# CHIBI_INPUT2_20171126.net
KiCad netlist of a schematic drawn in Altium Designer
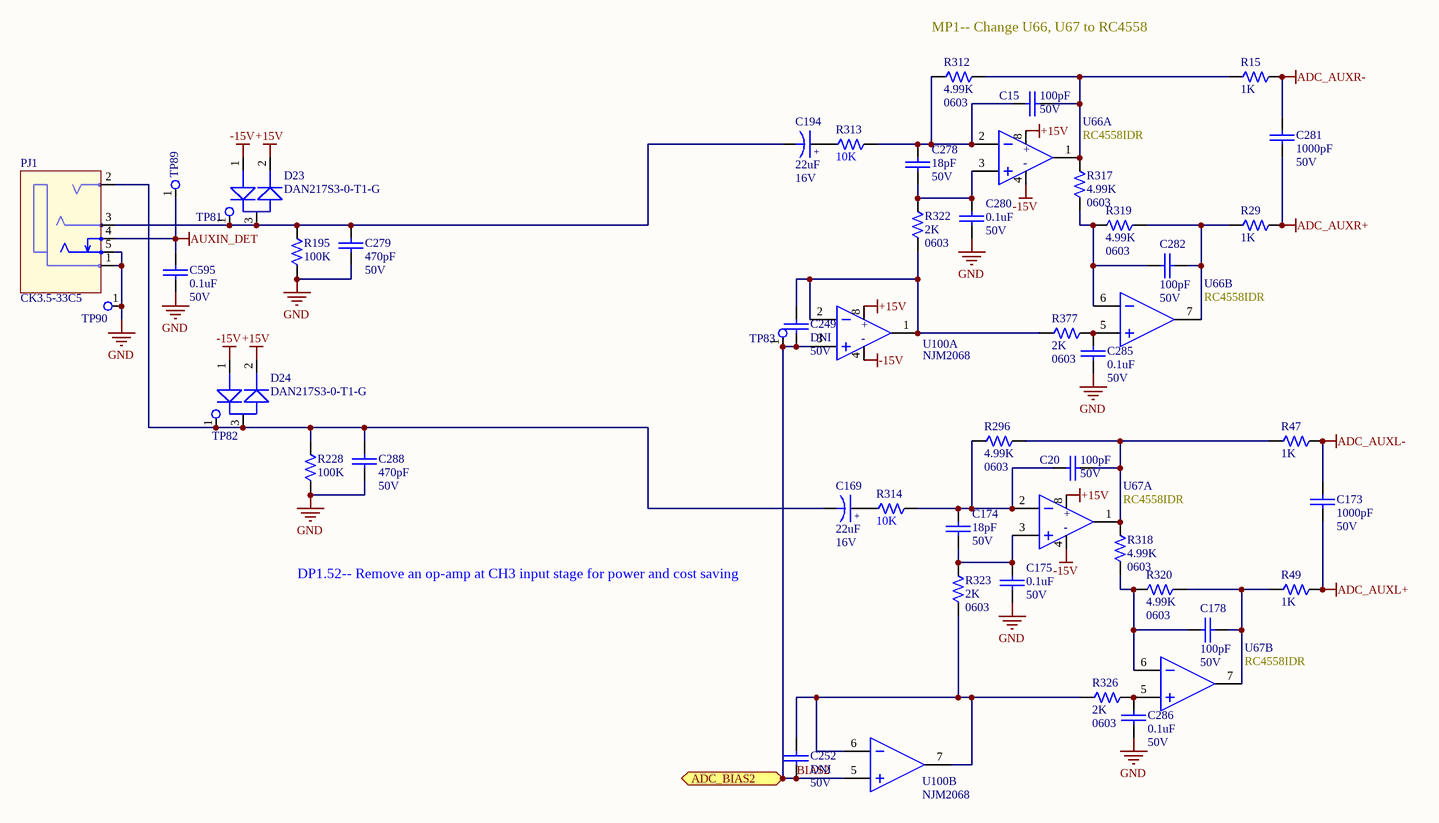
[diagram p0: CHIBI_INPUT2_20171126.SchDoc]

(export (version "E")
  (design (tool "Eeschema 10.0.6"))
  (components
    (comp (ref "C15")
      (value "100pF")
      (footprint "CAPC0603-RW")
      (description "GP CHIP CAP 100pF 50V 5% 0603 TYPE NPO")
      (fields
        (field (name "TOLERANCE") "5%")
        (field (name "VOLTAGE") "50V")
        (field (name "Comment") "PXL410370-1010")
      )
      (libsource (lib "P-Capacitors") (part "CAP0603 100pF 50V 5% - PXL410370-1010"))
    )
    (comp (ref "C20")
      (value "100pF")
      (footprint "CAPC0603-RW")
      (description "GP CHIP CAP 100pF 50V 5% 0603 TYPE NPO")
      (fields
        (field (name "TOLERANCE") "5%")
        (field (name "VOLTAGE") "50V")
        (field (name "Comment") "PXL410370-1010")
      )
      (libsource (lib "P-Capacitors") (part "CAP0603 100pF 50V 5% - PXL410370-1010"))
    )
    (comp (ref "C169")
      (value "22uF")
      (footprint "CASE - B")
      (description "E 22UF 16V +-20% 4X5.4M CK1C220M-CRC54 G")
      (fields
        (field (name "MFG") "NORMAL")
        (field (name "MFG PART") "CK1C220M-CRC54")
        (field (name "VOLTAGE") "16V")
      )
      (libsource (lib "P-Capacitors") (part "CAP E 22uF 16V 20% SMD_CASE-B"))
    )
    (comp (ref "C173")
      (value "1000pF")
      (footprint "CAPC0603-RW")
      (description "CHIP CAP 1000pF 50V 5% 0603 TYPE NPO")
      (fields
        (field (name "TOLERANCE") "5%")
        (field (name "VOLTAGE") "50V")
        (field (name "Comment") "PXL410370-1020")
      )
      (libsource (lib "P-Capacitors") (part "CAP0603 1000pF 50V 5% - PXL410370-1020"))
    )
    (comp (ref "C174")
      (value "18pF")
      (footprint "P-Capacitors:CAPC0603-RW")
      (description "CHIP CAP 18pF 50V 5% 0603 TYPE NPO")
      (fields
        (field (name "TOLERANCE") "5%")
        (field (name "VOLTAGE") "50V")
        (field (name "Comment") "PXL410370-1800")
      )
      (libsource (lib "P-Capacitors") (part "CAP0603 18pF 50V 5% - PXL410370-1800"))
    )
    (comp (ref "C175")
      (value "0.1uF")
      (footprint "CAPC0603-RW")
      (description "GP CHIP CAP 0.1uF 50V 10% 0603 TYPE X7R")
      (fields
        (field (name "TOLERANCE") "10%")
        (field (name "VOLTAGE") "50V")
        (field (name "Comment") "PXL456470-1040")
      )
      (libsource (lib "P-Capacitors") (part "CAP0603 0.1uF 50V 10% - PXL456470-1040"))
    )
    (comp (ref "C178")
      (value "100pF")
      (footprint "CAPC0603-RW")
      (description "GP CHIP CAP 100pF 50V 5% 0603 TYPE NPO")
      (fields
        (field (name "TOLERANCE") "5%")
        (field (name "VOLTAGE") "50V")
        (field (name "Comment") "PXL410370-1010")
      )
      (libsource (lib "P-Capacitors") (part "CAP0603 100pF 50V 5% - PXL410370-1010"))
    )
    (comp (ref "C194")
      (value "22uF")
      (footprint "CASE - B")
      (description "E 22UF 16V +-20% 4X5.4M CK1C220M-CRC54 G")
      (fields
        (field (name "MFG") "NORMAL")
        (field (name "MFG PART") "CK1C220M-CRC54")
        (field (name "VOLTAGE") "16V")
      )
      (libsource (lib "P-Capacitors") (part "CAP E 22uF 16V 20% SMD_CASE-B"))
    )
    (comp (ref "C249")
      (value "DNI")
      (footprint "CAPC0402-RW")
      (fields
        (field (name "TOLERANCE") "10%")
        (field (name "VOLTAGE") "50V")
        (field (name "CREATE_NAME") "Nathan")
      )
      (libsource (lib "P-Capacitors") (part "CAP0402 0.1uF 50V_10%_X7R_TDK"))
    )
    (comp (ref "C252")
      (value "DNI")
      (footprint "CAPC0402-RW")
      (fields
        (field (name "TOLERANCE") "10%")
        (field (name "VOLTAGE") "50V")
        (field (name "CREATE_NAME") "Nathan")
      )
      (libsource (lib "P-Capacitors") (part "CAP0402 0.1uF 50V_10%_X7R_TDK"))
    )
    (comp (ref "C278")
      (value "18pF")
      (footprint "P-Capacitors:CAPC0603-RW")
      (description "CHIP CAP 18pF 50V 5% 0603 TYPE NPO")
      (fields
        (field (name "TOLERANCE") "5%")
        (field (name "VOLTAGE") "50V")
        (field (name "Comment") "PXL410370-1800")
      )
      (libsource (lib "P-Capacitors") (part "CAP0603 18pF 50V 5% - PXL410370-1800"))
    )
    (comp (ref "C279")
      (value "470pF")
      (footprint "P-Capacitors:CAPC0603-RW")
      (description "GP CHIP CAP 470pF 50V 5% 0603 NPO")
      (fields
        (field (name "TOLERANCE") "5%")
        (field (name "VOLTAGE") "50V")
        (field (name "Comment") "PXL410370-4710")
      )
      (libsource (lib "P-Capacitors") (part "CAP0603 470pF 50V 5% - PXL410370-4710"))
    )
    (comp (ref "C280")
      (value "0.1uF")
      (footprint "CAPC0603-RW")
      (description "GP CHIP CAP 0.1uF 50V 10% 0603 TYPE X7R")
      (fields
        (field (name "TOLERANCE") "10%")
        (field (name "VOLTAGE") "50V")
        (field (name "Comment") "PXL456470-1040")
      )
      (libsource (lib "P-Capacitors") (part "CAP0603 0.1uF 50V 10% - PXL456470-1040"))
    )
    (comp (ref "C281")
      (value "1000pF")
      (footprint "CAPC0603-RW")
      (description "CHIP CAP 1000pF 50V 5% 0603 TYPE NPO")
      (fields
        (field (name "TOLERANCE") "5%")
        (field (name "VOLTAGE") "50V")
        (field (name "Comment") "PXL410370-1020")
      )
      (libsource (lib "P-Capacitors") (part "CAP0603 1000pF 50V 5% - PXL410370-1020"))
    )
    (comp (ref "C282")
      (value "100pF")
      (footprint "CAPC0603-RW")
      (description "GP CHIP CAP 100pF 50V 5% 0603 TYPE NPO")
      (fields
        (field (name "TOLERANCE") "5%")
        (field (name "VOLTAGE") "50V")
        (field (name "Comment") "PXL410370-1010")
      )
      (libsource (lib "P-Capacitors") (part "CAP0603 100pF 50V 5% - PXL410370-1010"))
    )
    (comp (ref "C285")
      (value "0.1uF")
      (footprint "CAPC0603-RW")
      (description "GP CHIP CAP 0.1uF 50V 10% 0603 TYPE X7R")
      (fields
        (field (name "TOLERANCE") "10%")
        (field (name "VOLTAGE") "50V")
        (field (name "Comment") "PXL456470-1040")
      )
      (libsource (lib "P-Capacitors") (part "CAP0603 0.1uF 50V 10% - PXL456470-1040"))
    )
    (comp (ref "C286")
      (value "0.1uF")
      (footprint "CAPC0603-RW")
      (description "GP CHIP CAP 0.1uF 50V 10% 0603 TYPE X7R")
      (fields
        (field (name "TOLERANCE") "10%")
        (field (name "VOLTAGE") "50V")
        (field (name "Comment") "PXL456470-1040")
      )
      (libsource (lib "P-Capacitors") (part "CAP0603 0.1uF 50V 10% - PXL456470-1040"))
    )
    (comp (ref "C288")
      (value "470pF")
      (footprint "P-Capacitors:CAPC0603-RW")
      (description "GP CHIP CAP 470pF 50V 5% 0603 NPO")
      (fields
        (field (name "TOLERANCE") "5%")
        (field (name "VOLTAGE") "50V")
        (field (name "Comment") "PXL410370-4710")
      )
      (libsource (lib "P-Capacitors") (part "CAP0603 470pF 50V 5% - PXL410370-4710"))
    )
    (comp (ref "C595")
      (value "0.1uF")
      (footprint "CAPC0402-RW")
      (description "CAP, CER, 0.1uF, 10%, 50V, X7R, 0402, RoHS")
      (fields
        (field (name "TOLERANCE") "10%")
        (field (name "VOLTAGE") "50V")
        (field (name "Comment") "PWL456470-1040")
        (field (name "CREATE_NAME") "TOM@Deftronics")
      )
      (libsource (lib "P-Capacitors") (part "CAP0402 0.1uF 50V 10%"))
    )
    (comp (ref "D23")
      (value "T572006171251")
      (footprint "SOT323(SC-70)-R")
      (description "ITC 100V 215MA DAN217S3-0-T1-G CYSTE K")
      (fields
        (field (name "MFG") "CYSTECH")
        (field (name "MFG PART") "DAN217S3-0-T1-G")
        (field (name "CREATE NAME") "Nathan")
      )
      (libsource (lib "R-Semiconductors") (part "DAN217S3-0-T1-G"))
    )
    (comp (ref "D24")
      (value "T572006171251")
      (footprint "SOT323(SC-70)-R")
      (description "ITC 100V 215MA DAN217S3-0-T1-G CYSTE K")
      (fields
        (field (name "MFG") "CYSTECH")
        (field (name "MFG PART") "DAN217S3-0-T1-G")
        (field (name "CREATE NAME") "Nathan")
      )
      (libsource (lib "R-Semiconductors") (part "DAN217S3-0-T1-G"))
    )
    (comp (ref "PJ1")
      (value "T710200010500")
      (footprint "Phone Jack CK3.5-33C5")
      (description "EARPHONE JACK K")
      (fields
        (field (name "MFG") "JINJIA")
        (field (name "MFG PART") "CK3.5-33C5")
        (field (name "CREATE_NAME") "Nathan")
      )
      (libsource (lib "C-Connector") (part "PHONE JACK 3.5mm CK3.5-33C5"))
    )
    (comp (ref "R15")
      (value "1K")
      (footprint "0402-RW")
      (description "CHIP RES 1K OHM 1/16W 1% 0402")
      (fields (field (name "MFG") "WALSIN") (field (name "Comment") "QCF161240-1001"))
      (libsource (lib "Q-Resistors") (part "RES0402 1/16W 1% 1K OHM"))
    )
    (comp (ref "R29")
      (value "1K")
      (footprint "0402-RW")
      (description "CHIP RES 1K OHM 1/16W 1% 0402")
      (fields (field (name "MFG") "WALSIN") (field (name "Comment") "QCF161240-1001"))
      (libsource (lib "Q-Resistors") (part "RES0402 1/16W 1% 1K OHM"))
    )
    (comp (ref "R47")
      (value "1K")
      (footprint "0402-RW")
      (description "CHIP RES 1K OHM 1/16W 1% 0402")
      (fields (field (name "MFG") "WALSIN") (field (name "Comment") "QCF161240-1001"))
      (libsource (lib "Q-Resistors") (part "RES0402 1/16W 1% 1K OHM"))
    )
    (comp (ref "R49")
      (value "1K")
      (footprint "0402-RW")
      (description "CHIP RES 1K OHM 1/16W 1% 0402")
      (fields (field (name "MFG") "WALSIN") (field (name "Comment") "QCF161240-1001"))
      (libsource (lib "Q-Resistors") (part "RES0402 1/16W 1% 1K OHM"))
    )
    (comp (ref "R195")
      (value "100K")
      (footprint "0603-RW")
      (description "GP CHIP RES. 100K OHM 1/10W 1% 0603")
      (fields (field (name "Comment") "QCF011030-1003"))
      (libsource (lib "Q-Resistors") (part "RES0603 1/10W 1% 100K OHM"))
    )
    (comp (ref "R228")
      (value "100K")
      (footprint "0603-RW")
      (description "GP CHIP RES. 100K OHM 1/10W 1% 0603")
      (fields (field (name "Comment") "QCF011030-1003"))
      (libsource (lib "Q-Resistors") (part "RES0603 1/10W 1% 100K OHM"))
    )
    (comp (ref "R296")
      (value "4.99K")
      (footprint "Q-Resistors:0603-RW")
      (description "GP CHIP RES. 4.99K OHM 1/10W 1% 0603")
      (fields (field (name "PACKAGE") "0603") (field (name "Comment") "QCF011030-4991"))
      (libsource (lib "Q-Resistors") (part "RES0603 1/10W 1% 4.99K OHM"))
    )
    (comp (ref "R312")
      (value "4.99K")
      (footprint "Q-Resistors:0603-RW")
      (description "GP CHIP RES. 4.99K OHM 1/10W 1% 0603")
      (fields (field (name "PACKAGE") "0603") (field (name "Comment") "QCF011030-4991"))
      (libsource (lib "Q-Resistors") (part "RES0603 1/10W 1% 4.99K OHM"))
    )
    (comp (ref "R313")
      (value "10K")
      (footprint "0603-RW")
      (description "GP CHIP RES. 10K OHM 1/10W 1% 0603")
      (fields (field (name "Comment") "QCF011030-1002"))
      (libsource (lib "Q-Resistors") (part "RES0603 1/10W 1% 10K OHM"))
    )
    (comp (ref "R314")
      (value "10K")
      (footprint "0603-RW")
      (description "GP CHIP RES. 10K OHM 1/10W 1% 0603")
      (fields (field (name "Comment") "QCF011030-1002"))
      (libsource (lib "Q-Resistors") (part "RES0603 1/10W 1% 10K OHM"))
    )
    (comp (ref "R317")
      (value "4.99K")
      (footprint "Q-Resistors:0603-RW")
      (description "GP CHIP RES. 4.99K OHM 1/10W 1% 0603")
      (fields (field (name "PACKAGE") "0603") (field (name "Comment") "QCF011030-4991"))
      (libsource (lib "Q-Resistors") (part "RES0603 1/10W 1% 4.99K OHM"))
    )
    (comp (ref "R318")
      (value "4.99K")
      (footprint "Q-Resistors:0603-RW")
      (description "GP CHIP RES. 4.99K OHM 1/10W 1% 0603")
      (fields (field (name "PACKAGE") "0603") (field (name "Comment") "QCF011030-4991"))
      (libsource (lib "Q-Resistors") (part "RES0603 1/10W 1% 4.99K OHM"))
    )
    (comp (ref "R319")
      (value "4.99K")
      (footprint "Q-Resistors:0603-RW")
      (description "GP CHIP RES. 4.99K OHM 1/10W 1% 0603")
      (fields (field (name "PACKAGE") "0603") (field (name "Comment") "QCF011030-4991"))
      (libsource (lib "Q-Resistors") (part "RES0603 1/10W 1% 4.99K OHM"))
    )
    (comp (ref "R320")
      (value "4.99K")
      (footprint "Q-Resistors:0603-RW")
      (description "GP CHIP RES. 4.99K OHM 1/10W 1% 0603")
      (fields (field (name "PACKAGE") "0603") (field (name "Comment") "QCF011030-4991"))
      (libsource (lib "Q-Resistors") (part "RES0603 1/10W 1% 4.99K OHM"))
    )
    (comp (ref "R322")
      (value "2K")
      (footprint "0603-RW")
      (description "GP CHIP RES. 2K OHM 1/10W 1% 0603")
      (fields (field (name "PACKAGE") "0603") (field (name "Comment") "QCF011030-2001"))
      (libsource (lib "Q-Resistors") (part "RES0603 1/10W 1% 2K OHM"))
    )
    (comp (ref "R323")
      (value "2K")
      (footprint "0603-RW")
      (description "GP CHIP RES. 2K OHM 1/10W 1% 0603")
      (fields (field (name "PACKAGE") "0603") (field (name "Comment") "QCF011030-2001"))
      (libsource (lib "Q-Resistors") (part "RES0603 1/10W 1% 2K OHM"))
    )
    (comp (ref "R326")
      (value "2K")
      (footprint "0603-RW")
      (description "GP CHIP RES. 2K OHM 1/10W 1% 0603")
      (fields (field (name "PACKAGE") "0603") (field (name "Comment") "QCF011030-2001"))
      (libsource (lib "Q-Resistors") (part "RES0603 1/10W 1% 2K OHM"))
    )
    (comp (ref "R377")
      (value "2K")
      (footprint "0603-RW")
      (description "GP CHIP RES. 2K OHM 1/10W 1% 0603")
      (fields (field (name "PACKAGE") "0603") (field (name "Comment") "QCF011030-2001"))
      (libsource (lib "Q-Resistors") (part "RES0603 1/10W 1% 2K OHM"))
    )
    (comp (ref "TP81")
      (value "CON3_2")
      (footprint "TP_1.2mm")
      (description "TP")
      (libsource (lib "Temporary") (part "TP"))
    )
    (comp (ref "TP82")
      (value "CON3_3")
      (footprint "TP_1.2mm")
      (description "TP")
      (libsource (lib "Temporary") (part "TP"))
    )
    (comp (ref "TP83")
      (value "CON3_2")
      (footprint "TP_1.2mm")
      (description "TP")
      (libsource (lib "Temporary") (part "TP"))
    )
    (comp (ref "TP89")
      (value "CON3_2")
      (footprint "TP_1.2mm")
      (description "TP")
      (libsource (lib "Temporary") (part "TP"))
    )
    (comp (ref "TP90")
      (value "CON3_2")
      (footprint "TP_1.2mm")
      (description "TP")
      (libsource (lib "Temporary") (part "TP"))
    )
    (comp (ref "U66")
      (value "T610500019101")
      (footprint "D(R-PDSO-G8)")
      (description "OP RC4558IDR SOP-8 TI G")
      (fields
        (field (name "MFG") "TI")
        (field (name "MFG PART") "RC4558IDR")
        (field (name "CREATE_NAME") "Nathan")
      )
      (libsource (lib "R-Semiconductors") (part "RC4558IDR"))
    )
    (comp (ref "U67")
      (value "T610500019101")
      (footprint "D(R-PDSO-G8)")
      (description "OP RC4558IDR SOP-8 TI G")
      (fields
        (field (name "MFG") "TI")
        (field (name "MFG PART") "RC4558IDR")
        (field (name "CREATE_NAME") "Nathan")
      )
      (libsource (lib "R-Semiconductors") (part "RC4558IDR"))
    )
    (comp (ref "U100")
      (value "RCI002068-0001")
      (footprint "DMP8")
      (description "IC OP AMP NJM2068 DUAL SO-8")
      (fields
        (field (name "MFG") "JRC")
        (field (name "MFG PART") "NJM2068")
        (field (name "CREATE_NAME") "GordonL@Deftronics")
      )
      (libsource (lib "R-Semiconductors") (part "NJM2068"))
    )
  )
  (nets
    (net (code "1") (name "+15V") (class "Default")
      (node (ref "D23") (pin "2") (pinfunction "K_2") (pintype "passive"))
      (node (ref "D24") (pin "2") (pinfunction "K_2") (pintype "passive"))
      (node (ref "U100") (pin "8") (pinfunction "8_8") (pintype "passive"))
      (node (ref "U66") (pin "8") (pinfunction "VCC+_8") (pintype "passive"))
      (node (ref "U67") (pin "8") (pinfunction "VCC+_8") (pintype "passive"))
    )
    (net (code "2") (name "-15V") (class "Default")
      (node (ref "D23") (pin "1") (pinfunction "A_1") (pintype "passive"))
      (node (ref "D24") (pin "1") (pinfunction "A_1") (pintype "passive"))
      (node (ref "U100") (pin "4") (pinfunction "4_4") (pintype "passive"))
      (node (ref "U66") (pin "4") (pinfunction "VCC-_4") (pintype "passive"))
      (node (ref "U67") (pin "4") (pinfunction "VCC-_4") (pintype "passive"))
    )
    (net (code "3") (name "/BIAS2") (class "Default")
      (node (ref "C249") (pin "2") (pinfunction "2_2") (pintype "passive"))
      (node (ref "C252") (pin "2") (pinfunction "2_2") (pintype "passive"))
      (node (ref "TP83") (pin "1") (pinfunction "1_1") (pintype "passive"))
      (node (ref "U100") (pin "3") (pinfunction "IN+_3") (pintype "passive"))
      (node (ref "U100") (pin "5") (pinfunction "IN+_5") (pintype "passive"))
    )
    (net (code "4") (name "ADC_AUXL+") (class "Default")
      (node (ref "C173") (pin "2") (pinfunction "2_2") (pintype "passive"))
      (node (ref "R49") (pin "2") (pinfunction "2_2") (pintype "passive"))
    )
    (net (code "5") (name "ADC_AUXL-") (class "Default")
      (node (ref "C173") (pin "1") (pinfunction "1_1") (pintype "passive"))
      (node (ref "R47") (pin "2") (pinfunction "2_2") (pintype "passive"))
    )
    (net (code "6") (name "ADC_AUXR+") (class "Default")
      (node (ref "C281") (pin "2") (pinfunction "2_2") (pintype "passive"))
      (node (ref "R29") (pin "2") (pinfunction "2_2") (pintype "passive"))
    )
    (net (code "7") (name "ADC_AUXR-") (class "Default")
      (node (ref "C281") (pin "1") (pinfunction "1_1") (pintype "passive"))
      (node (ref "R15") (pin "2") (pinfunction "2_2") (pintype "passive"))
    )
    (net (code "8") (name "AUXIN_DET") (class "Default")
      (node (ref "C595") (pin "1") (pinfunction "1_1") (pintype "passive"))
      (node (ref "PJ1") (pin "4") (pinfunction "4_4") (pintype "passive"))
      (node (ref "TP89") (pin "1") (pinfunction "1_1") (pintype "passive"))
    )
    (net (code "9") (name "GND") (class "Default")
      (node (ref "C175") (pin "2") (pinfunction "2_2") (pintype "passive"))
      (node (ref "C279") (pin "2") (pinfunction "2_2") (pintype "passive"))
      (node (ref "C280") (pin "2") (pinfunction "2_2") (pintype "passive"))
      (node (ref "C285") (pin "1") (pinfunction "1_1") (pintype "passive"))
      (node (ref "C286") (pin "1") (pinfunction "1_1") (pintype "passive"))
      (node (ref "C288") (pin "1") (pinfunction "1_1") (pintype "passive"))
      (node (ref "C595") (pin "2") (pinfunction "2_2") (pintype "passive"))
      (node (ref "PJ1") (pin "1") (pinfunction "1_1") (pintype "passive"))
      (node (ref "PJ1") (pin "5") (pinfunction "5_5") (pintype "passive"))
      (node (ref "R195") (pin "1") (pinfunction "1_1") (pintype "passive"))
      (node (ref "R228") (pin "1") (pinfunction "1_1") (pintype "passive"))
      (node (ref "TP90") (pin "1") (pinfunction "1_1") (pintype "passive"))
    )
    (net (code "10") (name "Net-(C169-Pad1)") (class "Default")
      (node (ref "C169") (pin "1") (pinfunction "1_1") (pintype "passive"))
      (node (ref "R314") (pin "1") (pinfunction "1_1") (pintype "passive"))
    )
    (net (code "11") (name "Net-(C194-Pad1)") (class "Default")
      (node (ref "C194") (pin "1") (pinfunction "1_1") (pintype "passive"))
      (node (ref "R313") (pin "1") (pinfunction "1_1") (pintype "passive"))
    )
    (net (code "12") (name "Net-(D23-C)") (class "Default")
      (node (ref "C194") (pin "2") (pinfunction "2_2") (pintype "passive"))
      (node (ref "C279") (pin "1") (pinfunction "1_1") (pintype "passive"))
      (node (ref "D23") (pin "3") (pinfunction "C_3") (pintype "passive"))
      (node (ref "PJ1") (pin "3") (pinfunction "3_3") (pintype "passive"))
      (node (ref "R195") (pin "2") (pinfunction "2_2") (pintype "passive"))
      (node (ref "TP81") (pin "1") (pinfunction "1_1") (pintype "passive"))
    )
    (net (code "13") (name "Net-(D24-C)") (class "Default")
      (node (ref "C169") (pin "2") (pinfunction "2_2") (pintype "passive"))
      (node (ref "C288") (pin "2") (pinfunction "2_2") (pintype "passive"))
      (node (ref "D24") (pin "3") (pinfunction "C_3") (pintype "passive"))
      (node (ref "PJ1") (pin "2") (pinfunction "2_2") (pintype "passive"))
      (node (ref "R228") (pin "2") (pinfunction "2_2") (pintype "passive"))
      (node (ref "TP82") (pin "1") (pinfunction "1_1") (pintype "passive"))
    )
    (net (code "14") (name "Net-(U66A-1IN+)") (class "Default")
      (node (ref "C278") (pin "2") (pinfunction "2_2") (pintype "passive"))
      (node (ref "C280") (pin "1") (pinfunction "1_1") (pintype "passive"))
      (node (ref "R322") (pin "2") (pinfunction "2_2") (pintype "passive"))
      (node (ref "U66") (pin "3") (pinfunction "1IN+_3") (pintype "passive"))
    )
    (net (code "15") (name "Net-(U66A-1IN-)") (class "Default")
      (node (ref "C15") (pin "1") (pinfunction "1_1") (pintype "passive"))
      (node (ref "C278") (pin "1") (pinfunction "1_1") (pintype "passive"))
      (node (ref "R312") (pin "1") (pinfunction "1_1") (pintype "passive"))
      (node (ref "R313") (pin "2") (pinfunction "2_2") (pintype "passive"))
      (node (ref "U66") (pin "2") (pinfunction "1IN-_2") (pintype "passive"))
    )
    (net (code "16") (name "Net-(U66A-1OUT)") (class "Default")
      (node (ref "C15") (pin "2") (pinfunction "2_2") (pintype "passive"))
      (node (ref "R15") (pin "1") (pinfunction "1_1") (pintype "passive"))
      (node (ref "R312") (pin "2") (pinfunction "2_2") (pintype "passive"))
      (node (ref "R317") (pin "2") (pinfunction "2_2") (pintype "passive"))
      (node (ref "U66") (pin "1") (pinfunction "1OUT_1") (pintype "passive"))
    )
    (net (code "17") (name "Net-(U66B-2IN+)") (class "Default")
      (node (ref "C285") (pin "2") (pinfunction "2_2") (pintype "passive"))
      (node (ref "R377") (pin "2") (pinfunction "2_2") (pintype "passive"))
      (node (ref "U66") (pin "5") (pinfunction "2IN+_5") (pintype "passive"))
    )
    (net (code "18") (name "Net-(U66B-2IN-)") (class "Default")
      (node (ref "C282") (pin "2") (pinfunction "2_2") (pintype "passive"))
      (node (ref "R317") (pin "1") (pinfunction "1_1") (pintype "passive"))
      (node (ref "R319") (pin "2") (pinfunction "2_2") (pintype "passive"))
      (node (ref "U66") (pin "6") (pinfunction "2IN-_6") (pintype "passive"))
    )
    (net (code "19") (name "Net-(U66B-2OUT)") (class "Default")
      (node (ref "C282") (pin "1") (pinfunction "1_1") (pintype "passive"))
      (node (ref "R29") (pin "1") (pinfunction "1_1") (pintype "passive"))
      (node (ref "R319") (pin "1") (pinfunction "1_1") (pintype "passive"))
      (node (ref "U66") (pin "7") (pinfunction "2OUT_7") (pintype "passive"))
    )
    (net (code "20") (name "Net-(U67A-1IN+)") (class "Default")
      (node (ref "C174") (pin "2") (pinfunction "2_2") (pintype "passive"))
      (node (ref "C175") (pin "1") (pinfunction "1_1") (pintype "passive"))
      (node (ref "R323") (pin "2") (pinfunction "2_2") (pintype "passive"))
      (node (ref "U67") (pin "3") (pinfunction "1IN+_3") (pintype "passive"))
    )
    (net (code "21") (name "Net-(U67A-1IN-)") (class "Default")
      (node (ref "C174") (pin "1") (pinfunction "1_1") (pintype "passive"))
      (node (ref "C20") (pin "1") (pinfunction "1_1") (pintype "passive"))
      (node (ref "R296") (pin "1") (pinfunction "1_1") (pintype "passive"))
      (node (ref "R314") (pin "2") (pinfunction "2_2") (pintype "passive"))
      (node (ref "U67") (pin "2") (pinfunction "1IN-_2") (pintype "passive"))
    )
    (net (code "22") (name "Net-(U67A-1OUT)") (class "Default")
      (node (ref "C20") (pin "2") (pinfunction "2_2") (pintype "passive"))
      (node (ref "R296") (pin "2") (pinfunction "2_2") (pintype "passive"))
      (node (ref "R318") (pin "2") (pinfunction "2_2") (pintype "passive"))
      (node (ref "R47") (pin "1") (pinfunction "1_1") (pintype "passive"))
      (node (ref "U67") (pin "1") (pinfunction "1OUT_1") (pintype "passive"))
    )
    (net (code "23") (name "Net-(U67B-2IN+)") (class "Default")
      (node (ref "C286") (pin "2") (pinfunction "2_2") (pintype "passive"))
      (node (ref "R326") (pin "2") (pinfunction "2_2") (pintype "passive"))
      (node (ref "U67") (pin "5") (pinfunction "2IN+_5") (pintype "passive"))
    )
    (net (code "24") (name "Net-(U67B-2IN-)") (class "Default")
      (node (ref "C178") (pin "2") (pinfunction "2_2") (pintype "passive"))
      (node (ref "R318") (pin "1") (pinfunction "1_1") (pintype "passive"))
      (node (ref "R320") (pin "2") (pinfunction "2_2") (pintype "passive"))
      (node (ref "U67") (pin "6") (pinfunction "2IN-_6") (pintype "passive"))
    )
    (net (code "25") (name "Net-(U67B-2OUT)") (class "Default")
      (node (ref "C178") (pin "1") (pinfunction "1_1") (pintype "passive"))
      (node (ref "R320") (pin "1") (pinfunction "1_1") (pintype "passive"))
      (node (ref "R49") (pin "1") (pinfunction "1_1") (pintype "passive"))
      (node (ref "U67") (pin "7") (pinfunction "2OUT_7") (pintype "passive"))
    )
    (net (code "26") (name "Net-(U100A-IN-)") (class "Default")
      (node (ref "C249") (pin "1") (pinfunction "1_1") (pintype "passive"))
      (node (ref "R322") (pin "1") (pinfunction "1_1") (pintype "passive"))
      (node (ref "R377") (pin "1") (pinfunction "1_1") (pintype "passive"))
      (node (ref "U100") (pin "1") (pinfunction "OUT_1") (pintype "passive"))
      (node (ref "U100") (pin "2") (pinfunction "IN-_2") (pintype "passive"))
    )
    (net (code "27") (name "Net-(U100B-IN-)") (class "Default")
      (node (ref "C252") (pin "1") (pinfunction "1_1") (pintype "passive"))
      (node (ref "R323") (pin "1") (pinfunction "1_1") (pintype "passive"))
      (node (ref "R326") (pin "1") (pinfunction "1_1") (pintype "passive"))
      (node (ref "U100") (pin "6") (pinfunction "IN-_6") (pintype "passive"))
      (node (ref "U100") (pin "7") (pinfunction "OUT_7") (pintype "passive"))
    )
  )
)
